# TSOC_GROVEY_UART.net
KiCad netlist of a schematic drawn in EAGLE
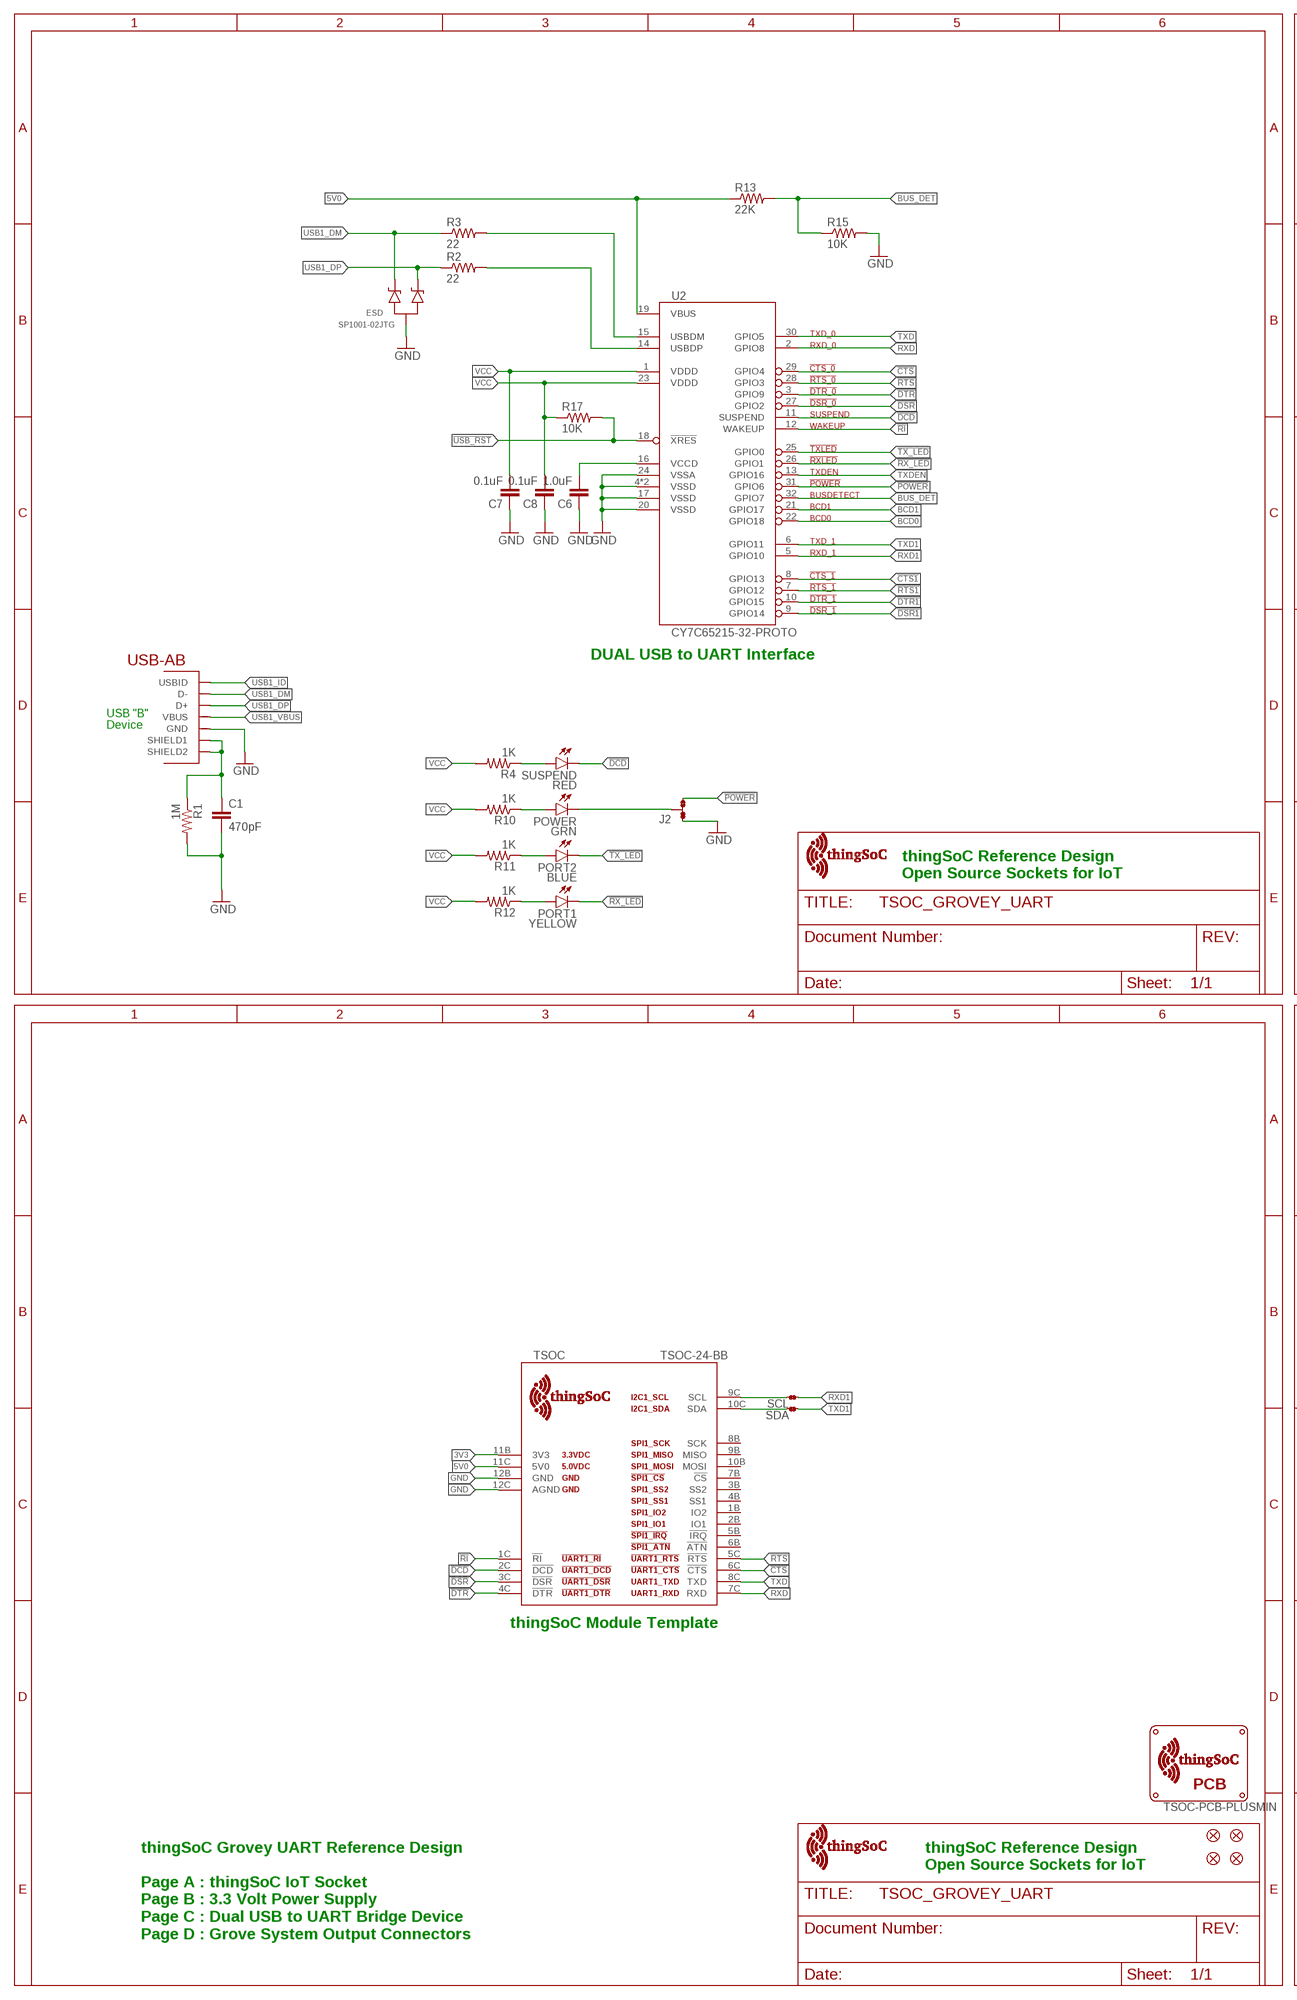
[diagram p0: schematic, sheet 1, part 1 of 2]
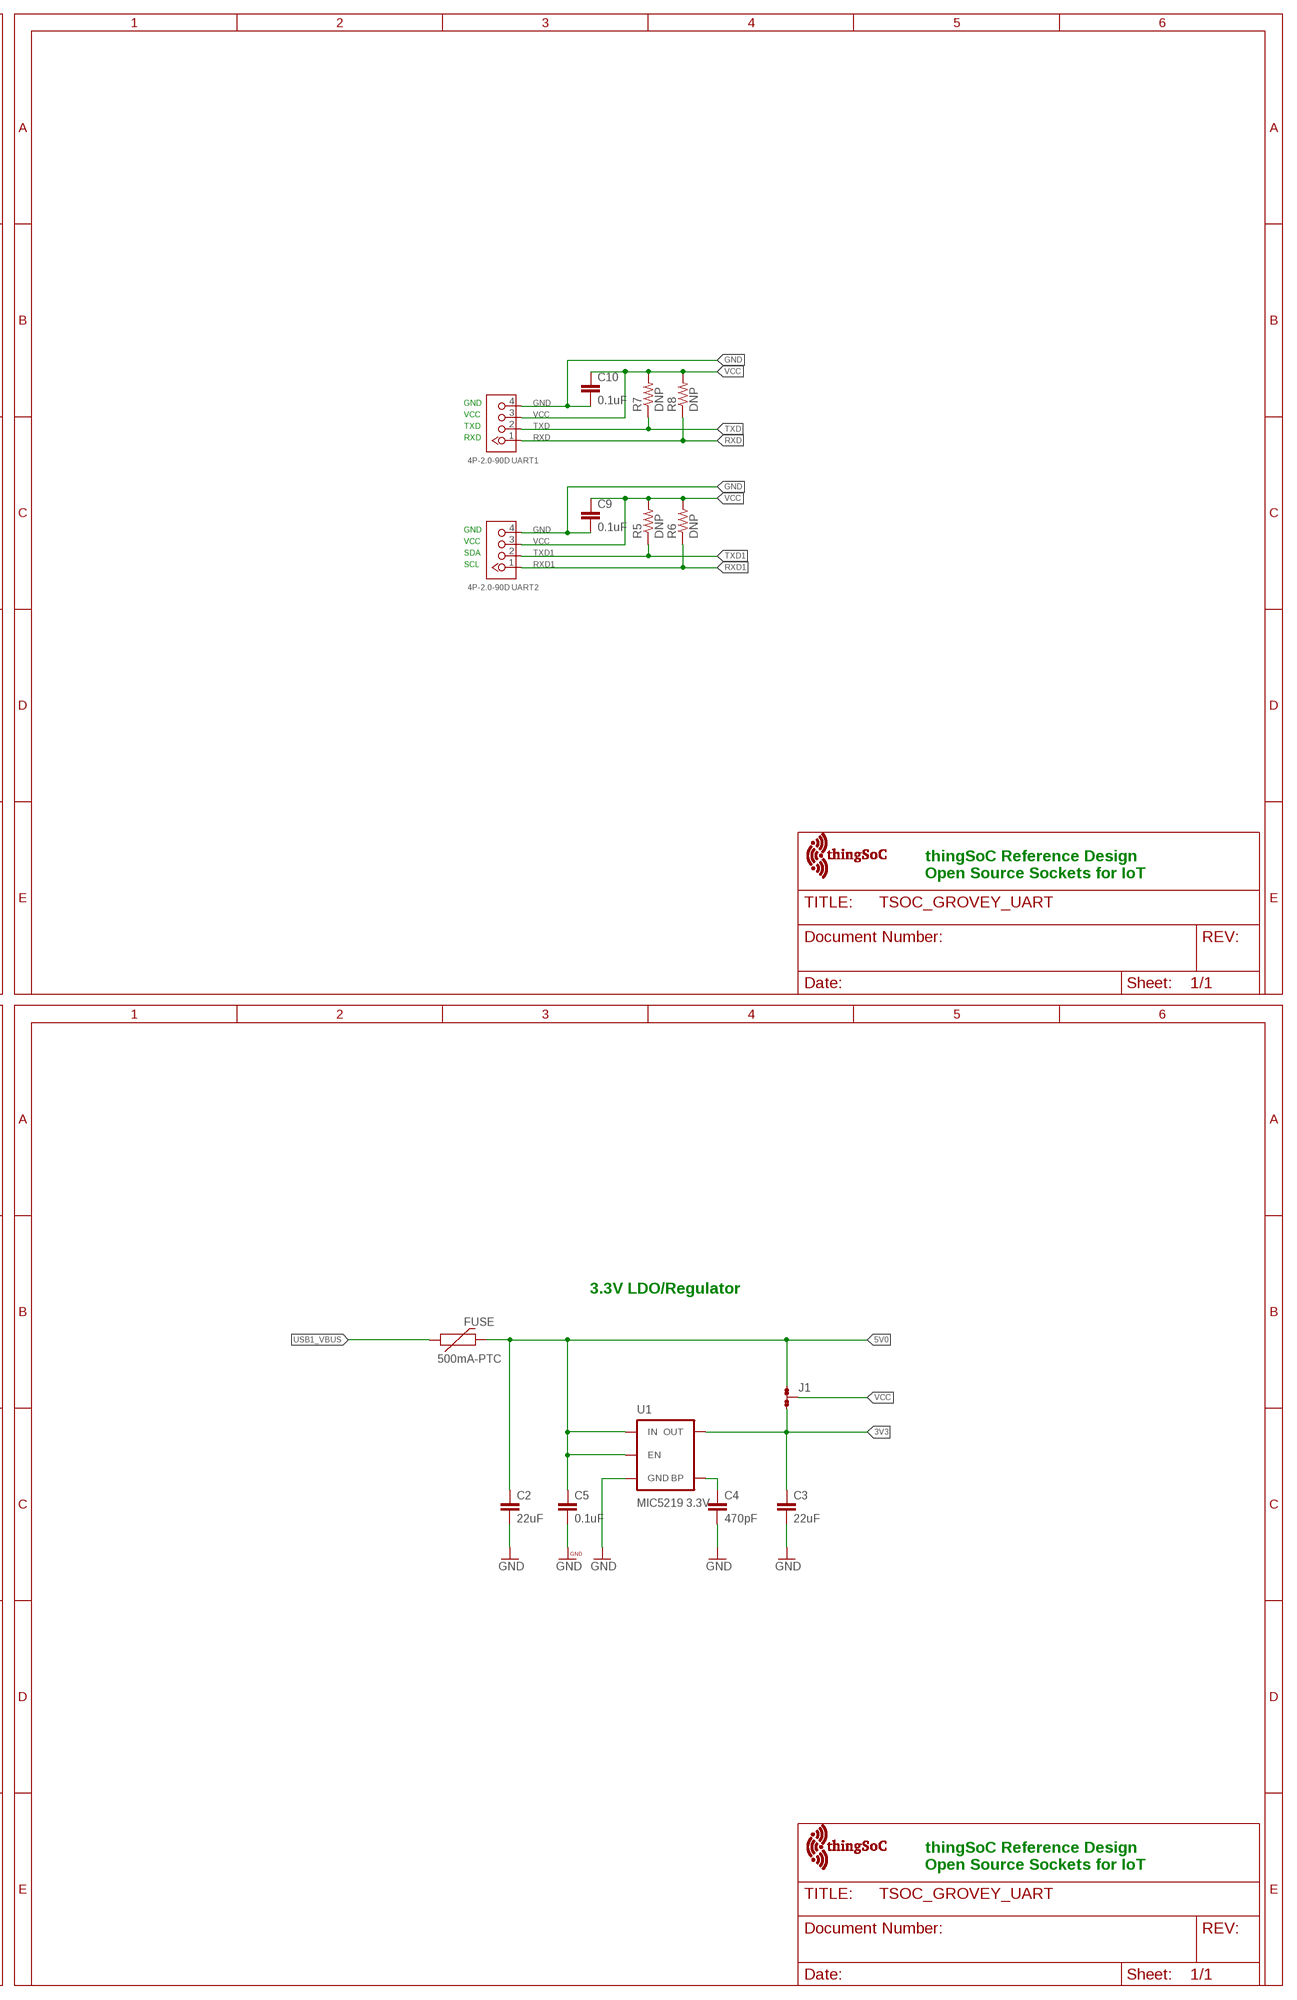
[diagram p1: schematic, sheet 1, part 2 of 2]

(export (version "E")
  (design (tool "Eeschema 10.0.6"))
  (components
    (comp (ref "C1")
      (value "470pF")
      (footprint "eagle-import:EIA-0603")
      (libsource (lib "eagle-import") (part "CAP-0603"))
    )
    (comp (ref "C2")
      (value "22uF")
      (footprint "eagle-import:EIA-1206")
      (libsource (lib "eagle-import") (part "CAP-1206"))
    )
    (comp (ref "C3")
      (value "22uF")
      (footprint "eagle-import:EIA-1206")
      (libsource (lib "eagle-import") (part "CAP-1206"))
    )
    (comp (ref "C4")
      (value "470pF")
      (footprint "eagle-import:EIA-0603")
      (libsource (lib "eagle-import") (part "CAP-0603"))
    )
    (comp (ref "C5")
      (value "0.1uF")
      (footprint "eagle-import:EIA-0603")
      (libsource (lib "eagle-import") (part "CAP-0603"))
    )
    (comp (ref "C6")
      (value "1.0uF")
      (footprint "eagle-import:EIA-0603")
      (libsource (lib "eagle-import") (part "CAP-0603"))
    )
    (comp (ref "C7")
      (value "0.1uF")
      (footprint "eagle-import:EIA-0603")
      (libsource (lib "eagle-import") (part "CAP-0603"))
    )
    (comp (ref "C8")
      (value "0.1uF")
      (footprint "eagle-import:EIA-0603")
      (libsource (lib "eagle-import") (part "CAP-0603"))
    )
    (comp (ref "C9")
      (value "0.1uF")
      (footprint "eagle-import:0603-CAP")
      (libsource (lib "eagle-import") (part "CAP0603-CAP"))
    )
    (comp (ref "C10")
      (value "0.1uF")
      (footprint "eagle-import:0603-CAP")
      (libsource (lib "eagle-import") (part "CAP0603-CAP"))
    )
    (comp (ref "ESD")
      (value "SP1001-02JTG")
      (footprint "eagle-import:SC70-3")
      (libsource (lib "eagle-import") (part "SP1001-02JTG"))
    )
    (comp (ref "FID1")
      (value "FIDUCIALUFIDUCIAL")
      (footprint "eagle-import:MICRO-FIDUCIAL")
      (libsource (lib "eagle-import") (part "FIDUCIALUFIDUCIAL"))
    )
    (comp (ref "FID2")
      (value "FIDUCIALUFIDUCIAL")
      (footprint "eagle-import:MICRO-FIDUCIAL")
      (libsource (lib "eagle-import") (part "FIDUCIALUFIDUCIAL"))
    )
    (comp (ref "FID3")
      (value "FIDUCIALUFIDUCIAL")
      (footprint "eagle-import:MICRO-FIDUCIAL")
      (libsource (lib "eagle-import") (part "FIDUCIALUFIDUCIAL"))
    )
    (comp (ref "FID4")
      (value "FIDUCIALUFIDUCIAL")
      (footprint "eagle-import:MICRO-FIDUCIAL")
      (libsource (lib "eagle-import") (part "FIDUCIALUFIDUCIAL"))
    )
    (comp (ref "FUSE")
      (value "500mA-PTC")
      (footprint "eagle-import:PTC-1206")
      (libsource (lib "eagle-import") (part "PTCSMD"))
    )
    (comp (ref "J1")
      (value "JMP-3-1_2")
      (footprint "eagle-import:JMP-3-1_2")
      (libsource (lib "eagle-import") (part "JMP-3-1_2"))
    )
    (comp (ref "J2")
      (value "JMP-3-1_2")
      (footprint "eagle-import:JMP-3-1_2")
      (libsource (lib "eagle-import") (part "JMP-3-1_2"))
    )
    (comp (ref "PCB")
      (value "TSOC-PCB-PLUSMIN")
      (footprint "eagle-import:TSOC-BB-BRD-PLUS-MIN-DIM")
      (libsource (lib "eagle-import") (part "TSOC-PCB-PLUSMIN"))
    )
    (comp (ref "PORT1")
      (value "YELLOW")
      (footprint "eagle-import:LED-0603")
      (libsource (lib "eagle-import") (part "LED0603"))
    )
    (comp (ref "PORT2")
      (value "BLUE")
      (footprint "eagle-import:LED-0603")
      (libsource (lib "eagle-import") (part "LED0603"))
    )
    (comp (ref "POWER")
      (value "GRN")
      (footprint "eagle-import:LED-0603")
      (libsource (lib "eagle-import") (part "LED0603"))
    )
    (comp (ref "R1")
      (value "1M")
      (footprint "eagle-import:EIA-0603")
      (libsource (lib "eagle-import") (part "RESISTOR-0603"))
    )
    (comp (ref "R2")
      (value "22")
      (footprint "eagle-import:EIA-0603")
      (libsource (lib "eagle-import") (part "RESISTOR-0603"))
    )
    (comp (ref "R3")
      (value "22")
      (footprint "eagle-import:EIA-0603")
      (libsource (lib "eagle-import") (part "RESISTOR-0603"))
    )
    (comp (ref "R4")
      (value "1K")
      (footprint "eagle-import:EIA-0603")
      (libsource (lib "eagle-import") (part "RESISTOR-0603"))
    )
    (comp (ref "R5")
      (value "DNP")
      (footprint "eagle-import:0603-RES")
      (libsource (lib "eagle-import") (part "RESISTOR0603-RES"))
    )
    (comp (ref "R6")
      (value "DNP")
      (footprint "eagle-import:0603-RES")
      (libsource (lib "eagle-import") (part "RESISTOR0603-RES"))
    )
    (comp (ref "R7")
      (value "DNP")
      (footprint "eagle-import:0603-RES")
      (libsource (lib "eagle-import") (part "RESISTOR0603-RES"))
    )
    (comp (ref "R8")
      (value "DNP")
      (footprint "eagle-import:0603-RES")
      (libsource (lib "eagle-import") (part "RESISTOR0603-RES"))
    )
    (comp (ref "R10")
      (value "1K")
      (footprint "eagle-import:EIA-0603")
      (libsource (lib "eagle-import") (part "RESISTOR-0603"))
    )
    (comp (ref "R11")
      (value "1K")
      (footprint "eagle-import:EIA-0603")
      (libsource (lib "eagle-import") (part "RESISTOR-0603"))
    )
    (comp (ref "R12")
      (value "1K")
      (footprint "eagle-import:EIA-0603")
      (libsource (lib "eagle-import") (part "RESISTOR-0603"))
    )
    (comp (ref "R13")
      (value "22K")
      (footprint "eagle-import:EIA-0603")
      (libsource (lib "eagle-import") (part "RESISTOR-0603"))
    )
    (comp (ref "R15")
      (value "10K")
      (footprint "eagle-import:EIA-0603")
      (libsource (lib "eagle-import") (part "RESISTOR-0603"))
    )
    (comp (ref "R17")
      (value "10K")
      (footprint "eagle-import:EIA-0603")
      (libsource (lib "eagle-import") (part "RESISTOR-0603"))
    )
    (comp (ref "SCL")
      (value "JMP-2-NO")
      (footprint "eagle-import:JMP-2-NO")
      (libsource (lib "eagle-import") (part "JMP-2-NO"))
    )
    (comp (ref "SDA")
      (value "JMP-2-NO")
      (footprint "eagle-import:JMP-2-NO")
      (libsource (lib "eagle-import") (part "JMP-2-NO"))
    )
    (comp (ref "SUSPEND")
      (value "RED")
      (footprint "eagle-import:LED-0603")
      (libsource (lib "eagle-import") (part "LED0603"))
    )
    (comp (ref "TSOC")
      (value "TSOC-24-BB")
      (footprint "eagle-import:TSOC-BB-S24")
      (libsource (lib "eagle-import") (part "TSOC-24-BB"))
    )
    (comp (ref "U$3")
      (value "TSOC-LOGO-LRG")
      (footprint "eagle-import:TSOC-LOGO-LRG")
      (libsource (lib "eagle-import") (part "TSOC-LOGO-LRG"))
    )
    (comp (ref "U$4")
      (value "TSOC-LOGO")
      (footprint "eagle-import:TSOC-LOGO-BLANK")
      (libsource (lib "eagle-import") (part "TSOC-LOGO"))
    )
    (comp (ref "U$5")
      (value "TSOC-LOGO")
      (footprint "eagle-import:TSOC-LOGO-BLANK")
      (libsource (lib "eagle-import") (part "TSOC-LOGO"))
    )
    (comp (ref "U$6")
      (value "TSOC-LOGO")
      (footprint "eagle-import:TSOC-LOGO-BLANK")
      (libsource (lib "eagle-import") (part "TSOC-LOGO"))
    )
    (comp (ref "U1")
      (value "MIC5219 3.3V")
      (footprint "eagle-import:SOT23-5")
      (libsource (lib "eagle-import") (part "V_REG_MIC52193.3V"))
    )
    (comp (ref "U2")
      (value "CY7C65215-32-PROTO")
      (footprint "eagle-import:QFN32-PROTO")
      (libsource (lib "eagle-import") (part "CY7C65215-32-PROTO"))
    )
    (comp (ref "UART1")
      (value "4P-2.0-90D")
      (footprint "eagle-import:HW4-2.0-90D")
      (libsource (lib "eagle-import") (part "GROVE-CONNECTOR-DIP-90D(4P-2.0)"))
    )
    (comp (ref "UART2")
      (value "4P-2.0-90D")
      (footprint "eagle-import:HW4-2.0-90D")
      (libsource (lib "eagle-import") (part "GROVE-CONNECTOR-DIP-90D(4P-2.0)"))
    )
    (comp (ref "USB")
      (value "USB_AB")
      (footprint "eagle-import:USB-AB-MICRO-SMD")
      (libsource (lib "eagle-import") (part "USB_AB"))
    )
  )
  (nets
    (net (code "1") (name "/~{CTS1}") (class "Default")
      (node (ref "U2") (pin "8") (pinfunction "GPIO13_8") (pintype "input"))
    )
    (net (code "2") (name "/~{CTS}") (class "Default")
      (node (ref "TSOC") (pin "6C") (pinfunction "~{CTS}_6C") (pintype "bidirectional"))
      (node (ref "U2") (pin "29") (pinfunction "GPIO4_29") (pintype "input"))
    )
    (net (code "3") (name "/~{DCD}") (class "Default")
      (node (ref "SUSPEND") (pin "C") (pinfunction "C_C") (pintype "passive"))
      (node (ref "TSOC") (pin "2C") (pinfunction "~{DCD}_2C") (pintype "bidirectional"))
      (node (ref "U2") (pin "11") (pinfunction "SUSPEND_11") (pintype "input"))
    )
    (net (code "4") (name "/~{DSR1}") (class "Default")
      (node (ref "U2") (pin "9") (pinfunction "GPIO14_9") (pintype "input"))
    )
    (net (code "5") (name "/~{DSR}") (class "Default")
      (node (ref "TSOC") (pin "3C") (pinfunction "~{DSR}_3C") (pintype "bidirectional"))
      (node (ref "U2") (pin "27") (pinfunction "GPIO2_27") (pintype "input"))
    )
    (net (code "6") (name "/~{DTR1}") (class "Default")
      (node (ref "U2") (pin "10") (pinfunction "GPIO15_10") (pintype "output"))
    )
    (net (code "7") (name "/~{DTR}") (class "Default")
      (node (ref "TSOC") (pin "4C") (pinfunction "~{DTR}_4C") (pintype "bidirectional"))
      (node (ref "U2") (pin "3") (pinfunction "GPIO9_3") (pintype "output"))
    )
    (net (code "8") (name "/~{POWER}") (class "Default")
      (node (ref "J2") (pin "3") (pinfunction "3_3") (pintype "passive"))
      (node (ref "U2") (pin "31") (pinfunction "GPIO6_31") (pintype "input"))
    )
    (net (code "9") (name "/~{RI}") (class "Default")
      (node (ref "TSOC") (pin "1C") (pinfunction "~{RI}_1C") (pintype "bidirectional"))
      (node (ref "U2") (pin "12") (pinfunction "WAKEUP_12") (pintype "input"))
    )
    (net (code "10") (name "/~{RTS1}") (class "Default")
      (node (ref "U2") (pin "7") (pinfunction "GPIO12_7") (pintype "output"))
    )
    (net (code "11") (name "/~{RTS}") (class "Default")
      (node (ref "TSOC") (pin "5C") (pinfunction "~{RTS}_5C") (pintype "bidirectional"))
      (node (ref "U2") (pin "28") (pinfunction "GPIO3_28") (pintype "output"))
    )
    (net (code "12") (name "/~{RX_LED}") (class "Default")
      (node (ref "PORT1") (pin "C") (pinfunction "C_C") (pintype "passive"))
      (node (ref "U2") (pin "26") (pinfunction "GPIO1_26") (pintype "input"))
    )
    (net (code "13") (name "/~{TX_LED}") (class "Default")
      (node (ref "PORT2") (pin "C") (pinfunction "C_C") (pintype "passive"))
      (node (ref "U2") (pin "25") (pinfunction "GPIO0_25") (pintype "input"))
    )
    (net (code "14") (name "/~{USB_RST}") (class "Default")
      (node (ref "R17") (pin "2") (pinfunction "2_2") (pintype "passive"))
      (node (ref "U2") (pin "18") (pinfunction "~{XRES}_18") (pintype "input"))
    )
    (net (code "15") (name "3V3") (class "Default")
      (node (ref "C3") (pin "1") (pinfunction "1_1") (pintype "passive"))
      (node (ref "J1") (pin "3") (pinfunction "3_3") (pintype "passive"))
      (node (ref "TSOC") (pin "11B") (pinfunction "3V3_11B") (pintype "bidirectional"))
      (node (ref "U1") (pin "5") (pinfunction "OUT_5") (pintype "passive"))
    )
    (net (code "16") (name "5V0") (class "Default")
      (node (ref "C2") (pin "1") (pinfunction "1_1") (pintype "passive"))
      (node (ref "C5") (pin "1") (pinfunction "1_1") (pintype "passive"))
      (node (ref "FUSE") (pin "2") (pinfunction "2_2") (pintype "bidirectional"))
      (node (ref "J1") (pin "1") (pinfunction "1_1") (pintype "passive"))
      (node (ref "R13") (pin "1") (pinfunction "1_1") (pintype "passive"))
      (node (ref "TSOC") (pin "11C") (pinfunction "5V0_11C") (pintype "bidirectional"))
      (node (ref "U1") (pin "1") (pinfunction "IN_1") (pintype "input"))
      (node (ref "U1") (pin "3") (pinfunction "EN_3") (pintype "input"))
      (node (ref "U2") (pin "19") (pinfunction "VBUS_19") (pintype "power_in"))
    )
    (net (code "17") (name "BCD0") (class "Default")
      (node (ref "U2") (pin "22") (pinfunction "GPIO18_22") (pintype "input"))
    )
    (net (code "18") (name "BCD1") (class "Default")
      (node (ref "U2") (pin "21") (pinfunction "GPIO17_21") (pintype "input"))
    )
    (net (code "19") (name "BUS_DET") (class "Default")
      (node (ref "R13") (pin "2") (pinfunction "2_2") (pintype "passive"))
      (node (ref "R15") (pin "1") (pinfunction "1_1") (pintype "passive"))
      (node (ref "U2") (pin "32") (pinfunction "GPIO7_32") (pintype "input"))
    )
    (net (code "20") (name "GND") (class "Default")
      (node (ref "C1") (pin "2") (pinfunction "2_2") (pintype "passive"))
      (node (ref "C10") (pin "2") (pinfunction "2_2") (pintype "passive"))
      (node (ref "C2") (pin "2") (pinfunction "2_2") (pintype "passive"))
      (node (ref "C3") (pin "2") (pinfunction "2_2") (pintype "passive"))
      (node (ref "C4") (pin "2") (pinfunction "2_2") (pintype "passive"))
      (node (ref "C5") (pin "2") (pinfunction "2_2") (pintype "passive"))
      (node (ref "C6") (pin "1") (pinfunction "1_1") (pintype "passive"))
      (node (ref "C7") (pin "1") (pinfunction "1_1") (pintype "passive"))
      (node (ref "C8") (pin "1") (pinfunction "1_1") (pintype "passive"))
      (node (ref "C9") (pin "2") (pinfunction "2_2") (pintype "passive"))
      (node (ref "ESD") (pin "3") (pinfunction "A_3") (pintype "passive"))
      (node (ref "J2") (pin "1") (pinfunction "1_1") (pintype "passive"))
      (node (ref "R1") (pin "2") (pinfunction "2_2") (pintype "passive"))
      (node (ref "R15") (pin "2") (pinfunction "2_2") (pintype "passive"))
      (node (ref "TSOC") (pin "12B") (pinfunction "GND_12B") (pintype "bidirectional"))
      (node (ref "TSOC") (pin "12C") (pinfunction "AGND_12C") (pintype "bidirectional"))
      (node (ref "U1") (pin "2") (pinfunction "GND_2") (pintype "input"))
      (node (ref "U2") (pin "17") (pinfunction "VSSD_17") (pintype "power_in"))
      (node (ref "U2") (pin "20") (pinfunction "VSSD_20") (pintype "power_in"))
      (node (ref "U2") (pin "24") (pinfunction "VSSA_24") (pintype "power_in"))
      (node (ref "U2") (pin "4") (pinfunction "VSSD_4") (pintype "power_in"))
      (node (ref "U2") (pin "EXP") (pinfunction "VSSD_EXP") (pintype "power_in"))
      (node (ref "UART1") (pin "4") (pinfunction "4_4") (pintype "bidirectional"))
      (node (ref "UART2") (pin "4") (pinfunction "4_4") (pintype "bidirectional"))
      (node (ref "USB") (pin "GND") (pinfunction "GND_GND") (pintype "bidirectional"))
    )
    (net (code "21") (name "Net-(C1-Pad1)") (class "Default")
      (node (ref "C1") (pin "1") (pinfunction "1_1") (pintype "passive"))
      (node (ref "R1") (pin "1") (pinfunction "1_1") (pintype "passive"))
      (node (ref "USB") (pin "SHIELD1") (pinfunction "SHIELD1_SHIELD1") (pintype "bidirectional"))
      (node (ref "USB") (pin "SHIELD2") (pinfunction "SHIELD2_SHIELD2") (pintype "bidirectional"))
    )
    (net (code "22") (name "Net-(J2-Pad2)") (class "Default")
      (node (ref "J2") (pin "2") (pinfunction "2_2") (pintype "passive"))
      (node (ref "POWER") (pin "C") (pinfunction "C_C") (pintype "passive"))
    )
    (net (code "23") (name "Net-(PORT1-PadA)") (class "Default")
      (node (ref "PORT1") (pin "A") (pinfunction "A_A") (pintype "passive"))
      (node (ref "R12") (pin "1") (pinfunction "1_1") (pintype "passive"))
    )
    (net (code "24") (name "Net-(PORT2-PadA)") (class "Default")
      (node (ref "PORT2") (pin "A") (pinfunction "A_A") (pintype "passive"))
      (node (ref "R11") (pin "1") (pinfunction "1_1") (pintype "passive"))
    )
    (net (code "25") (name "Net-(POWER-PadA)") (class "Default")
      (node (ref "POWER") (pin "A") (pinfunction "A_A") (pintype "passive"))
      (node (ref "R10") (pin "1") (pinfunction "1_1") (pintype "passive"))
    )
    (net (code "26") (name "Net-(R4-Pad1)") (class "Default")
      (node (ref "R4") (pin "1") (pinfunction "1_1") (pintype "passive"))
      (node (ref "SUSPEND") (pin "A") (pinfunction "A_A") (pintype "passive"))
    )
    (net (code "27") (name "Net-(TSOC-SCL)") (class "Default")
      (node (ref "SCL") (pin "2") (pinfunction "2_2") (pintype "passive"))
      (node (ref "TSOC") (pin "9C") (pinfunction "SCL_9C") (pintype "bidirectional"))
    )
    (net (code "28") (name "Net-(TSOC-SDA)") (class "Default")
      (node (ref "SDA") (pin "2") (pinfunction "2_2") (pintype "passive"))
      (node (ref "TSOC") (pin "10C") (pinfunction "SDA_10C") (pintype "bidirectional"))
    )
    (net (code "29") (name "Net-(U1-BP)") (class "Default")
      (node (ref "C4") (pin "1") (pinfunction "1_1") (pintype "passive"))
      (node (ref "U1") (pin "4") (pinfunction "BP_4") (pintype "input"))
    )
    (net (code "30") (name "Net-(U2-USBDM)") (class "Default")
      (node (ref "R3") (pin "2") (pinfunction "2_2") (pintype "passive"))
      (node (ref "U2") (pin "15") (pinfunction "USBDM_15") (pintype "bidirectional"))
    )
    (net (code "31") (name "Net-(U2-USBDP)") (class "Default")
      (node (ref "R2") (pin "2") (pinfunction "2_2") (pintype "passive"))
      (node (ref "U2") (pin "14") (pinfunction "USBDP_14") (pintype "bidirectional"))
    )
    (net (code "32") (name "Net-(U2-VCCD)") (class "Default")
      (node (ref "C6") (pin "2") (pinfunction "2_2") (pintype "passive"))
      (node (ref "U2") (pin "16") (pinfunction "VCCD_16") (pintype "output"))
    )
    (net (code "33") (name "RXD") (class "Default")
      (node (ref "R8") (pin "1") (pinfunction "1_1") (pintype "passive"))
      (node (ref "TSOC") (pin "7C") (pinfunction "RXD_7C") (pintype "bidirectional"))
      (node (ref "U2") (pin "2") (pinfunction "GPIO8_2") (pintype "input"))
      (node (ref "UART1") (pin "1") (pinfunction "1_1") (pintype "bidirectional"))
    )
    (net (code "34") (name "RXD1") (class "Default")
      (node (ref "R6") (pin "1") (pinfunction "1_1") (pintype "passive"))
      (node (ref "SCL") (pin "1") (pinfunction "1_1") (pintype "passive"))
      (node (ref "U2") (pin "5") (pinfunction "GPIO10_5") (pintype "input"))
      (node (ref "UART2") (pin "1") (pinfunction "1_1") (pintype "bidirectional"))
    )
    (net (code "35") (name "TXD") (class "Default")
      (node (ref "R7") (pin "1") (pinfunction "1_1") (pintype "passive"))
      (node (ref "TSOC") (pin "8C") (pinfunction "TXD_8C") (pintype "bidirectional"))
      (node (ref "U2") (pin "30") (pinfunction "GPIO5_30") (pintype "output"))
      (node (ref "UART1") (pin "2") (pinfunction "2_2") (pintype "bidirectional"))
    )
    (net (code "36") (name "TXD1") (class "Default")
      (node (ref "R5") (pin "1") (pinfunction "1_1") (pintype "passive"))
      (node (ref "SDA") (pin "1") (pinfunction "1_1") (pintype "passive"))
      (node (ref "U2") (pin "6") (pinfunction "GPIO11_6") (pintype "output"))
      (node (ref "UART2") (pin "2") (pinfunction "2_2") (pintype "bidirectional"))
    )
    (net (code "37") (name "TXDEN") (class "Default")
      (node (ref "U2") (pin "13") (pinfunction "GPIO16_13") (pintype "output"))
    )
    (net (code "38") (name "USB1_DM") (class "Default")
      (node (ref "ESD") (pin "2") (pinfunction "C2_2") (pintype "passive"))
      (node (ref "R3") (pin "1") (pinfunction "1_1") (pintype "passive"))
      (node (ref "USB") (pin "D-") (pinfunction "D-_D-") (pintype "bidirectional"))
    )
    (net (code "39") (name "USB1_DP") (class "Default")
      (node (ref "ESD") (pin "1") (pinfunction "C1_1") (pintype "passive"))
      (node (ref "R2") (pin "1") (pinfunction "1_1") (pintype "passive"))
      (node (ref "USB") (pin "D+") (pinfunction "D+_D+") (pintype "bidirectional"))
    )
    (net (code "40") (name "USB1_ID") (class "Default")
      (node (ref "USB") (pin "ID") (pinfunction "USBID_ID") (pintype "bidirectional"))
    )
    (net (code "41") (name "USB1_VBUS") (class "Default")
      (node (ref "FUSE") (pin "1") (pinfunction "1_1") (pintype "bidirectional"))
      (node (ref "USB") (pin "VBUS") (pinfunction "VBUS_VBUS") (pintype "bidirectional"))
    )
    (net (code "42") (name "VCC") (class "Default")
      (node (ref "C10") (pin "1") (pinfunction "1_1") (pintype "passive"))
      (node (ref "C7") (pin "2") (pinfunction "2_2") (pintype "passive"))
      (node (ref "C8") (pin "2") (pinfunction "2_2") (pintype "passive"))
      (node (ref "C9") (pin "1") (pinfunction "1_1") (pintype "passive"))
      (node (ref "J1") (pin "2") (pinfunction "2_2") (pintype "passive"))
      (node (ref "R10") (pin "2") (pinfunction "2_2") (pintype "passive"))
      (node (ref "R11") (pin "2") (pinfunction "2_2") (pintype "passive"))
      (node (ref "R12") (pin "2") (pinfunction "2_2") (pintype "passive"))
      (node (ref "R17") (pin "1") (pinfunction "1_1") (pintype "passive"))
      (node (ref "R4") (pin "2") (pinfunction "2_2") (pintype "passive"))
      (node (ref "R5") (pin "2") (pinfunction "2_2") (pintype "passive"))
      (node (ref "R6") (pin "2") (pinfunction "2_2") (pintype "passive"))
      (node (ref "R7") (pin "2") (pinfunction "2_2") (pintype "passive"))
      (node (ref "R8") (pin "2") (pinfunction "2_2") (pintype "passive"))
      (node (ref "U2") (pin "1") (pinfunction "VDDD_1") (pintype "power_in"))
      (node (ref "U2") (pin "23") (pinfunction "VDDD_23") (pintype "power_in"))
      (node (ref "UART1") (pin "3") (pinfunction "3_3") (pintype "bidirectional"))
      (node (ref "UART2") (pin "3") (pinfunction "3_3") (pintype "bidirectional"))
    )
    (net (code "43") (name "unconnected-(TSOC-IO1-Pad2B)") (class "Default")
      (node (ref "TSOC") (pin "2B") (pinfunction "IO1_2B") (pintype "bidirectional"))
    )
    (net (code "44") (name "unconnected-(TSOC-IO2-Pad1B)") (class "Default")
      (node (ref "TSOC") (pin "1B") (pinfunction "IO2_1B") (pintype "bidirectional"))
    )
    (net (code "45") (name "unconnected-(TSOC-MISO-Pad9B)") (class "Default")
      (node (ref "TSOC") (pin "9B") (pinfunction "MISO_9B") (pintype "bidirectional"))
    )
    (net (code "46") (name "unconnected-(TSOC-MOSI-Pad10B)") (class "Default")
      (node (ref "TSOC") (pin "10B") (pinfunction "MOSI_10B") (pintype "bidirectional"))
    )
    (net (code "47") (name "unconnected-(TSOC-SCK-Pad8B)") (class "Default")
      (node (ref "TSOC") (pin "8B") (pinfunction "SCK_8B") (pintype "bidirectional"))
    )
    (net (code "48") (name "unconnected-(TSOC-SS1-Pad4B)") (class "Default")
      (node (ref "TSOC") (pin "4B") (pinfunction "SS1_4B") (pintype "bidirectional"))
    )
    (net (code "49") (name "unconnected-(TSOC-SS2-Pad3B)") (class "Default")
      (node (ref "TSOC") (pin "3B") (pinfunction "SS2_3B") (pintype "bidirectional"))
    )
    (net (code "50") (name "unconnected-(TSOC-~{ATN}-Pad6B)") (class "Default")
      (node (ref "TSOC") (pin "6B") (pinfunction "~{ATN}_6B") (pintype "bidirectional"))
    )
    (net (code "51") (name "unconnected-(TSOC-~{CS}-Pad7B)") (class "Default")
      (node (ref "TSOC") (pin "7B") (pinfunction "~{CS}_7B") (pintype "bidirectional"))
    )
    (net (code "52") (name "unconnected-(TSOC-~{IRQ}-Pad5B)") (class "Default")
      (node (ref "TSOC") (pin "5B") (pinfunction "~{IRQ}_5B") (pintype "bidirectional"))
    )
  )
)
